# control.net
KiCad netlist of a schematic drawn in Altium Designer
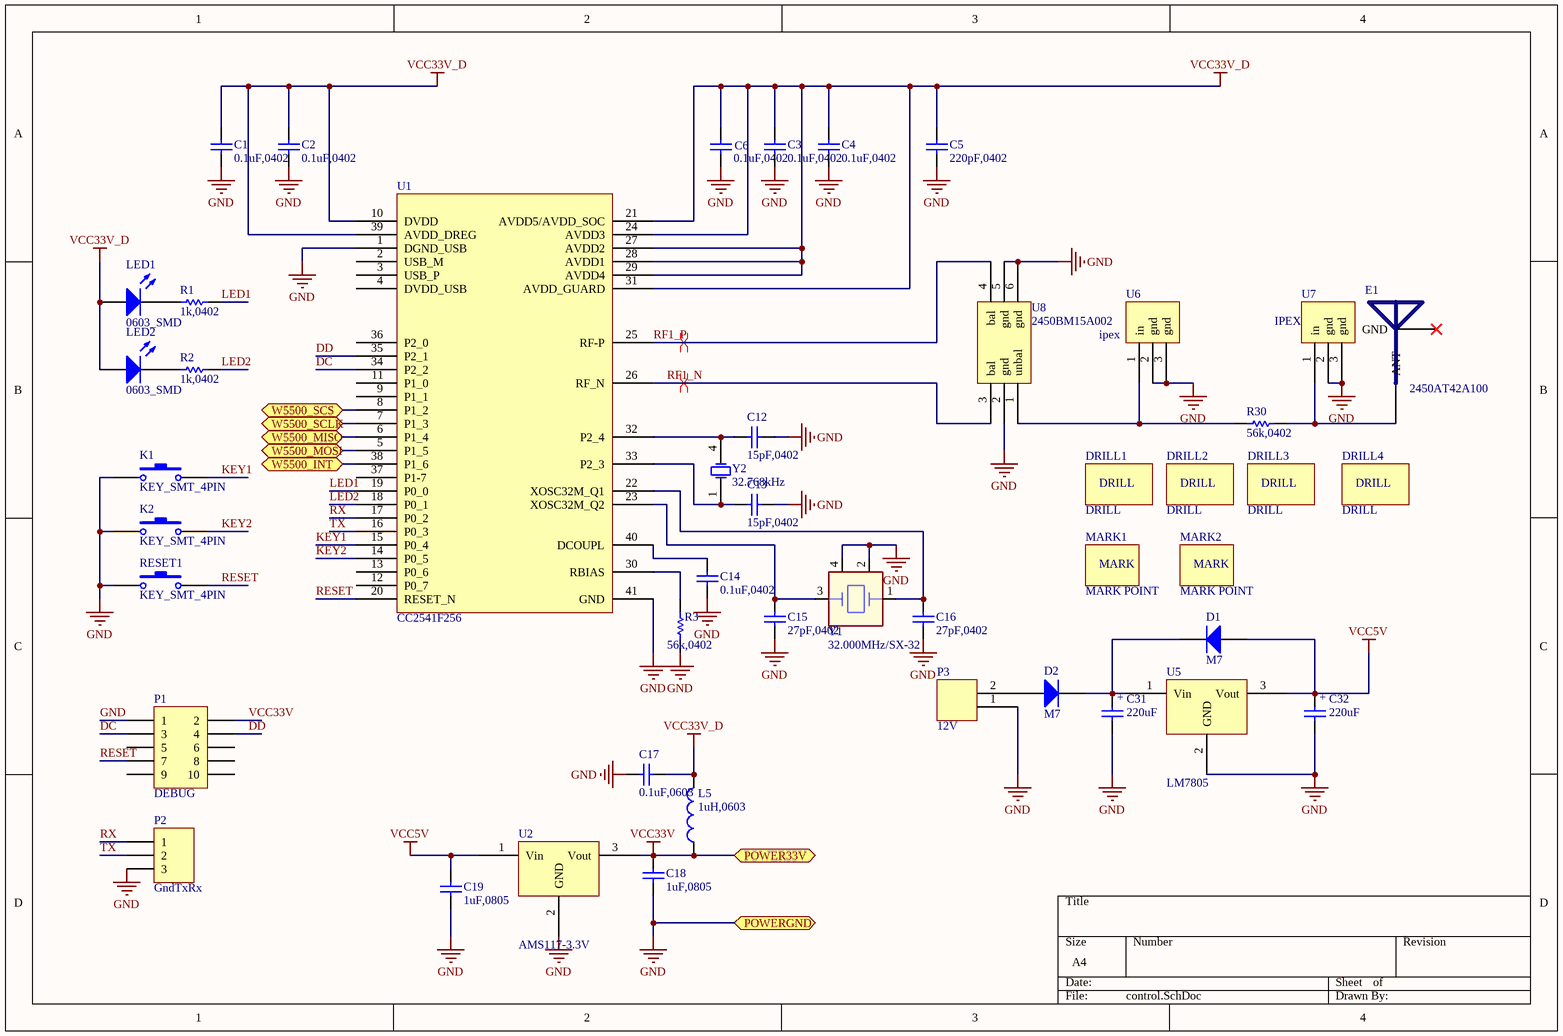
[diagram p0: control.SchDoc]

(export (version "E")
  (design (tool "Eeschema 10.0.6"))
  (components
    (comp (ref "C1")
      (value "0.1uF,0402")
      (footprint "C0402")
      (description "Capacitor")
      (fields (field (name "PUBLISHER") "Altium Limited"))
      (libsource (lib "Inte") (part "CAP"))
    )
    (comp (ref "C2")
      (value "0.1uF,0402")
      (footprint "C0402")
      (description "Capacitor")
      (fields (field (name "PUBLISHER") "Altium Limited"))
      (libsource (lib "Inte") (part "CAP"))
    )
    (comp (ref "C3")
      (value "0.1uF,0402")
      (footprint "C0402")
      (description "Capacitor")
      (fields (field (name "PUBLISHER") "Altium Limited"))
      (libsource (lib "Inte") (part "CAP"))
    )
    (comp (ref "C4")
      (value "0.1uF,0402")
      (footprint "C0402")
      (description "Capacitor")
      (fields (field (name "PUBLISHER") "Altium Limited"))
      (libsource (lib "Inte") (part "CAP"))
    )
    (comp (ref "C5")
      (value "220pF,0402")
      (footprint "C0402")
      (description "Capacitor")
      (fields (field (name "PUBLISHER") "Altium Limited"))
      (libsource (lib "Inte") (part "CAP"))
    )
    (comp (ref "C6")
      (value "0.1uF,0402")
      (footprint "C0402")
      (description "Capacitor")
      (fields (field (name "PUBLISHER") "Altium Limited"))
      (libsource (lib "Inte") (part "CAP"))
    )
    (comp (ref "C12")
      (value "15pF,0402")
      (footprint "C0402")
      (description "Capacitor")
      (fields (field (name "PUBLISHER") "Altium Limited"))
      (libsource (lib "Inte") (part "CAP"))
    )
    (comp (ref "C13")
      (value "15pF,0402")
      (footprint "C0402")
      (description "Capacitor")
      (fields (field (name "PUBLISHER") "Altium Limited"))
      (libsource (lib "Inte") (part "CAP"))
    )
    (comp (ref "C14")
      (value "0.1uF,0402")
      (footprint "C0402")
      (description "Capacitor")
      (fields (field (name "PUBLISHER") "Altium Limited"))
      (libsource (lib "Inte") (part "CAP"))
    )
    (comp (ref "C15")
      (value "27pF,0402")
      (footprint "C0402")
      (description "Capacitor")
      (fields (field (name "PUBLISHER") "Altium Limited"))
      (libsource (lib "Inte") (part "CAP"))
    )
    (comp (ref "C16")
      (value "27pF,0402")
      (footprint "C0402")
      (description "Capacitor")
      (fields (field (name "PUBLISHER") "Altium Limited"))
      (libsource (lib "Inte") (part "CAP"))
    )
    (comp (ref "C17")
      (value "0.1uF,0603")
      (footprint "C0603")
      (description "Capacitor")
      (fields (field (name "PUBLISHER") "Altium Limited"))
      (libsource (lib "Inte") (part "CAP"))
    )
    (comp (ref "C18")
      (value "1uF,0805")
      (footprint "C0805")
      (description "Capacitor")
      (fields (field (name "PUBLISHER") "Altium Limited"))
      (libsource (lib "Inte") (part "CAP"))
    )
    (comp (ref "C19")
      (value "1uF,0805")
      (footprint "C0805")
      (description "Capacitor")
      (fields (field (name "PUBLISHER") "Altium Limited"))
      (libsource (lib "Inte") (part "CAP"))
    )
    (comp (ref "C31")
      (value "220uF")
      (footprint "CDIP2")
      (description "electric capacitor")
      (libsource (lib "Inte") (part "E_CAP"))
    )
    (comp (ref "C32")
      (value "220uF")
      (footprint "CDIP2")
      (description "electric capacitor")
      (libsource (lib "Inte") (part "E_CAP"))
    )
    (comp (ref "D1")
      (value "M7")
      (footprint "DO214AC")
      (description "diode")
      (libsource (lib "Inte") (part "DIODE"))
    )
    (comp (ref "D2")
      (value "M7")
      (footprint "DO214AC")
      (description "diode")
      (libsource (lib "Inte") (part "DIODE"))
    )
    (comp (ref "DRILL1") (value "DRILL") (footprint "DRILL_3MM") (libsource (lib "Inte") (part "DRILL")))
    (comp (ref "DRILL2") (value "DRILL") (footprint "DRILL_3MM") (libsource (lib "Inte") (part "DRILL")))
    (comp (ref "DRILL3") (value "DRILL") (footprint "DRILL_3MM") (libsource (lib "Inte") (part "DRILL")))
    (comp (ref "DRILL4") (value "DRILL") (footprint "DRILL_3MM") (libsource (lib "Inte") (part "DRILL")))
    (comp (ref "E1")
      (value "2450AT42A100")
      (footprint "BT_ANT_PCB")
      (libsource (lib "Inte") (part "BT_ANT_PCB"))
    )
    (comp (ref "K1")
      (value "KEY_SMT_4PIN")
      (footprint "KEY-SMT")
      (description "key")
      (libsource (lib "Inte") (part "KEY"))
    )
    (comp (ref "K2")
      (value "KEY_SMT_4PIN")
      (footprint "KEY-SMT")
      (description "key")
      (libsource (lib "Inte") (part "KEY"))
    )
    (comp (ref "L5")
      (value "1uH,0603")
      (footprint "L0603")
      (description "Inductor")
      (fields (field (name "PUBLISHER") "Altium Limited"))
      (libsource (lib "Inte") (part "Inductor"))
    )
    (comp (ref "LED1")
      (value "0603_SMD")
      (footprint "LED0603")
      (description "led")
      (libsource (lib "Inte") (part "LED"))
    )
    (comp (ref "LED2")
      (value "0603_SMD")
      (footprint "LED0603")
      (description "led")
      (libsource (lib "Inte") (part "LED"))
    )
    (comp (ref "MARK1")
      (value "MARK POINT")
      (footprint "MARK_POINT")
      (libsource (lib "Inte") (part "MARK_POINT"))
    )
    (comp (ref "MARK2")
      (value "MARK POINT")
      (footprint "MARK_POINT")
      (libsource (lib "Inte") (part "MARK_POINT"))
    )
    (comp (ref "P1")
      (value "DEBUG")
      (footprint "HDR2X5")
      (description "Header, 5-Pin, Dual row")
      (fields (field (name "PUBLISHER") "Altium Limited"))
      (libsource (lib "Inte") (part "Header 5X2"))
    )
    (comp (ref "P2")
      (value "GndTxRx")
      (footprint "HDR1X3")
      (description "Header, 3-Pin")
      (fields (field (name "PUBLISHER") "Altium Limited"))
      (libsource (lib "Miscellaneous Connectors") (part "Header 3"))
    )
    (comp (ref "P3") (value "12V") (footprint "2EDG-5.08-2P") (libsource (lib "Inte") (part "2EDG-5.08-2P")))
    (comp (ref "R1")
      (value "1k,0402")
      (footprint "R0402")
      (description "Resistor")
      (fields (field (name "PUBLISHER") "Altium Limited"))
      (libsource (lib "Inte") (part "Res1"))
    )
    (comp (ref "R2")
      (value "1k,0402")
      (footprint "R0402")
      (description "Resistor")
      (fields (field (name "PUBLISHER") "Altium Limited"))
      (libsource (lib "Inte") (part "Res1"))
    )
    (comp (ref "R3")
      (value "56k,0402")
      (footprint "R0402")
      (description "Resistor")
      (fields (field (name "PUBLISHER") "Altium Limited"))
      (libsource (lib "Inte") (part "Res1"))
    )
    (comp (ref "R30")
      (value "56k,0402")
      (footprint "R0805")
      (description "Resistor")
      (fields (field (name "PUBLISHER") "Altium Limited"))
      (libsource (lib "Inte") (part "Res1"))
    )
    (comp (ref "RESET1")
      (value "KEY_SMT_4PIN")
      (footprint "KEY-SMT")
      (description "key")
      (libsource (lib "Inte") (part "KEY"))
    )
    (comp (ref "U1")
      (value "CC2541F256")
      (footprint "PQFP40")
      (description "TI cc2541F256")
      (libsource (lib "Inte") (part "CC254x"))
    )
    (comp (ref "U2")
      (value "AMS117-3.3V")
      (footprint "SOT223")
      (description "voltage regulator tube")
      (libsource (lib "Inte") (part "VOLT_REG"))
    )
    (comp (ref "U5")
      (value "LM7805")
      (footprint "SOT252")
      (description "voltage regulator tube")
      (libsource (lib "Inte") (part "VOLT_REG"))
    )
    (comp (ref "U6") (value "ipex") (footprint "IPEX") (libsource (lib "Inte") (part "IPEX")))
    (comp (ref "U7") (value "IPEX") (footprint "IPEX") (libsource (lib "Inte") (part "IPEX")))
    (comp (ref "U8")
      (value "2450BM15A002")
      (footprint "2450BM15A002")
      (libsource (lib "Inte") (part "2450BM15A002"))
    )
    (comp (ref "Y1")
      (value "32.000MHz/SX-32")
      (footprint "3225")
      (description "SPXO")
      (libsource (lib "Inte") (part "CRYSTAL_5"))
    )
    (comp (ref "Y2")
      (value "32.768kHz")
      (footprint "1206")
      (description "crystal")
      (libsource (lib "Inte") (part "DA740C"))
    )
  )
  (nets
    (net (code "1") (name "/DC") (class "Default")
      (node (ref "P1") (pin "3") (pinfunction "3_3") (pintype "passive"))
      (node (ref "U1") (pin "34") (pinfunction "P2_2_34") (pintype "passive"))
    )
    (net (code "2") (name "/DD") (class "Default")
      (node (ref "P1") (pin "4") (pinfunction "4_4") (pintype "passive"))
      (node (ref "U1") (pin "35") (pinfunction "P2_1_35") (pintype "passive"))
    )
    (net (code "3") (name "/KEY1") (class "Default")
      (node (ref "K1") (pin "2") (pinfunction "2_2") (pintype "passive"))
      (node (ref "U1") (pin "15") (pinfunction "P0_4_15") (pintype "passive"))
    )
    (net (code "4") (name "/KEY2") (class "Default")
      (node (ref "K2") (pin "2") (pinfunction "2_2") (pintype "passive"))
      (node (ref "U1") (pin "14") (pinfunction "P0_5_14") (pintype "passive"))
    )
    (net (code "5") (name "/LED1") (class "Default")
      (node (ref "R1") (pin "2") (pinfunction "2_2") (pintype "passive"))
      (node (ref "U1") (pin "19") (pinfunction "P0_0_19") (pintype "passive"))
    )
    (net (code "6") (name "/LED2") (class "Default")
      (node (ref "R2") (pin "2") (pinfunction "2_2") (pintype "passive"))
      (node (ref "U1") (pin "18") (pinfunction "P0_1_18") (pintype "passive"))
    )
    (net (code "7") (name "/RESET") (class "Default")
      (node (ref "P1") (pin "7") (pinfunction "7_7") (pintype "passive"))
      (node (ref "RESET1") (pin "2") (pinfunction "2_2") (pintype "passive"))
      (node (ref "U1") (pin "20") (pinfunction "RESET_N_20") (pintype "passive"))
    )
    (net (code "8") (name "/RF1_N") (class "Default")
      (node (ref "U1") (pin "26") (pinfunction "RF_N_26") (pintype "passive"))
      (node (ref "U8") (pin "3") (pinfunction "bal_3") (pintype "passive"))
    )
    (net (code "9") (name "/RF1_P") (class "Default")
      (node (ref "U1") (pin "25") (pinfunction "RF-P_25") (pintype "passive"))
      (node (ref "U8") (pin "4") (pinfunction "bal_4") (pintype "passive"))
    )
    (net (code "10") (name "/RX") (class "Default")
      (node (ref "P2") (pin "1") (pinfunction "1_1") (pintype "passive"))
      (node (ref "U1") (pin "17") (pinfunction "P0_2_17") (pintype "passive"))
    )
    (net (code "11") (name "/TX") (class "Default")
      (node (ref "P2") (pin "2") (pinfunction "2_2") (pintype "passive"))
      (node (ref "U1") (pin "16") (pinfunction "P0_3_16") (pintype "passive"))
    )
    (net (code "12") (name "/W5500_INT") (class "Default")
      (node (ref "U1") (pin "38") (pinfunction "P1_6_38") (pintype "passive"))
    )
    (net (code "13") (name "/W5500_MISO") (class "Default")
      (node (ref "U1") (pin "6") (pinfunction "P1_4_6") (pintype "passive"))
    )
    (net (code "14") (name "/W5500_MOSI") (class "Default")
      (node (ref "U1") (pin "5") (pinfunction "P1_5_5") (pintype "passive"))
    )
    (net (code "15") (name "/W5500_SCLK") (class "Default")
      (node (ref "U1") (pin "7") (pinfunction "P1_3_7") (pintype "passive"))
    )
    (net (code "16") (name "/W5500_SCS") (class "Default")
      (node (ref "U1") (pin "8") (pinfunction "P1_2_8") (pintype "passive"))
    )
    (net (code "17") (name "GND") (class "Default")
      (node (ref "C1") (pin "1") (pinfunction "1_1") (pintype "passive"))
      (node (ref "C12") (pin "1") (pinfunction "1_1") (pintype "passive"))
      (node (ref "C13") (pin "1") (pinfunction "1_1") (pintype "passive"))
      (node (ref "C14") (pin "1") (pinfunction "1_1") (pintype "passive"))
      (node (ref "C15") (pin "1") (pinfunction "1_1") (pintype "passive"))
      (node (ref "C16") (pin "1") (pinfunction "1_1") (pintype "passive"))
      (node (ref "C17") (pin "2") (pinfunction "2_2") (pintype "passive"))
      (node (ref "C18") (pin "1") (pinfunction "1_1") (pintype "passive"))
      (node (ref "C19") (pin "1") (pinfunction "1_1") (pintype "passive"))
      (node (ref "C2") (pin "1") (pinfunction "1_1") (pintype "passive"))
      (node (ref "C3") (pin "1") (pinfunction "1_1") (pintype "passive"))
      (node (ref "C31") (pin "2") (pinfunction "2_2") (pintype "passive"))
      (node (ref "C32") (pin "2") (pinfunction "2_2") (pintype "passive"))
      (node (ref "C4") (pin "1") (pinfunction "1_1") (pintype "passive"))
      (node (ref "C5") (pin "1") (pinfunction "1_1") (pintype "passive"))
      (node (ref "C6") (pin "2") (pinfunction "2_2") (pintype "passive"))
      (node (ref "K1") (pin "1") (pinfunction "1_1") (pintype "passive"))
      (node (ref "K2") (pin "1") (pinfunction "1_1") (pintype "passive"))
      (node (ref "P1") (pin "1") (pinfunction "1_1") (pintype "passive"))
      (node (ref "P2") (pin "3") (pinfunction "3_3") (pintype "passive"))
      (node (ref "P3") (pin "1") (pinfunction "1_1") (pintype "passive"))
      (node (ref "R3") (pin "1") (pinfunction "1_1") (pintype "passive"))
      (node (ref "RESET1") (pin "1") (pinfunction "1_1") (pintype "passive"))
      (node (ref "U1") (pin "1") (pinfunction "DGND_USB_1") (pintype "passive"))
      (node (ref "U1") (pin "41") (pinfunction "GND_41") (pintype "passive"))
      (node (ref "U2") (pin "2") (pinfunction "GND_2") (pintype "passive"))
      (node (ref "U5") (pin "2") (pinfunction "GND_2") (pintype "passive"))
      (node (ref "U6") (pin "2") (pinfunction "gnd_2") (pintype "passive"))
      (node (ref "U6") (pin "3") (pinfunction "gnd_3") (pintype "passive"))
      (node (ref "U7") (pin "2") (pinfunction "gnd_2") (pintype "passive"))
      (node (ref "U7") (pin "3") (pinfunction "gnd_3") (pintype "passive"))
      (node (ref "U8") (pin "2") (pinfunction "gnd_2") (pintype "passive"))
      (node (ref "U8") (pin "5") (pinfunction "gnd_5") (pintype "passive"))
      (node (ref "U8") (pin "6") (pinfunction "gnd_6") (pintype "passive"))
      (node (ref "Y1") (pin "2") (pinfunction "2_2") (pintype "passive"))
      (node (ref "Y1") (pin "4") (pinfunction "4_4") (pintype "passive"))
    )
    (net (code "18") (name "Net-(D1-K)") (class "Default")
      (node (ref "C31") (pin "1") (pinfunction "1_1") (pintype "passive"))
      (node (ref "D1") (pin "2") (pinfunction "K_2") (pintype "passive"))
      (node (ref "D2") (pin "2") (pinfunction "K_2") (pintype "passive"))
      (node (ref "U5") (pin "1") (pinfunction "Vin_1") (pintype "passive"))
    )
    (net (code "19") (name "Net-(D2-A)") (class "Default")
      (node (ref "D2") (pin "1") (pinfunction "A_1") (pintype "passive"))
      (node (ref "P3") (pin "2") (pinfunction "2_2") (pintype "passive"))
    )
    (net (code "20") (name "Net-(E1-ANT)") (class "Default")
      (node (ref "E1") (pin "1") (pinfunction "ANT_1") (pintype "passive"))
      (node (ref "R30") (pin "2") (pinfunction "2_2") (pintype "passive"))
      (node (ref "U7") (pin "1") (pinfunction "in_1") (pintype "passive"))
    )
    (net (code "21") (name "Net-(LED1-K)") (class "Default")
      (node (ref "LED1") (pin "2") (pinfunction "K_2") (pintype "passive"))
      (node (ref "R1") (pin "1") (pinfunction "1_1") (pintype "passive"))
    )
    (net (code "22") (name "Net-(LED2-K)") (class "Default")
      (node (ref "LED2") (pin "2") (pinfunction "K_2") (pintype "passive"))
      (node (ref "R2") (pin "1") (pinfunction "1_1") (pintype "passive"))
    )
    (net (code "23") (name "Net-(U1-DCOUPL)") (class "Default")
      (node (ref "C14") (pin "2") (pinfunction "2_2") (pintype "passive"))
      (node (ref "U1") (pin "40") (pinfunction "DCOUPL_40") (pintype "passive"))
    )
    (net (code "24") (name "Net-(U1-P2_3)") (class "Default")
      (node (ref "C13") (pin "2") (pinfunction "2_2") (pintype "passive"))
      (node (ref "U1") (pin "33") (pinfunction "P2_3_33") (pintype "passive"))
      (node (ref "Y2") (pin "1") (pinfunction "OSC1_1") (pintype "passive"))
    )
    (net (code "25") (name "Net-(U1-P2_4)") (class "Default")
      (node (ref "C12") (pin "2") (pinfunction "2_2") (pintype "passive"))
      (node (ref "U1") (pin "32") (pinfunction "P2_4_32") (pintype "passive"))
      (node (ref "Y2") (pin "4") (pinfunction "OSC2_4") (pintype "passive"))
    )
    (net (code "26") (name "Net-(U1-RBIAS)") (class "Default")
      (node (ref "R3") (pin "2") (pinfunction "2_2") (pintype "passive"))
      (node (ref "U1") (pin "30") (pinfunction "RBIAS_30") (pintype "passive"))
    )
    (net (code "27") (name "Net-(U1-XOSC32M_Q1)") (class "Default")
      (node (ref "C16") (pin "2") (pinfunction "2_2") (pintype "passive"))
      (node (ref "U1") (pin "22") (pinfunction "XOSC32M_Q1_22") (pintype "passive"))
      (node (ref "Y1") (pin "1") (pinfunction "1_1") (pintype "passive"))
    )
    (net (code "28") (name "Net-(U1-XOSC32M_Q2)") (class "Default")
      (node (ref "C15") (pin "2") (pinfunction "2_2") (pintype "passive"))
      (node (ref "U1") (pin "23") (pinfunction "XOSC32M_Q2_23") (pintype "passive"))
      (node (ref "Y1") (pin "3") (pinfunction "3_3") (pintype "passive"))
    )
    (net (code "29") (name "Net-(U6-in)") (class "Default")
      (node (ref "R30") (pin "1") (pinfunction "1_1") (pintype "passive"))
      (node (ref "U6") (pin "1") (pinfunction "in_1") (pintype "passive"))
      (node (ref "U8") (pin "1") (pinfunction "unbal_1") (pintype "passive"))
    )
    (net (code "30") (name "VCC5V") (class "Default")
      (node (ref "C19") (pin "2") (pinfunction "2_2") (pintype "passive"))
      (node (ref "C32") (pin "1") (pinfunction "1_1") (pintype "passive"))
      (node (ref "D1") (pin "1") (pinfunction "A_1") (pintype "passive"))
      (node (ref "U2") (pin "1") (pinfunction "Vin_1") (pintype "passive"))
      (node (ref "U5") (pin "3") (pinfunction "Vout_3") (pintype "passive"))
    )
    (net (code "31") (name "VCC33V") (class "Default")
      (node (ref "C18") (pin "2") (pinfunction "2_2") (pintype "passive"))
      (node (ref "L5") (pin "1") (pinfunction "1_1") (pintype "passive"))
      (node (ref "P1") (pin "2") (pinfunction "2_2") (pintype "passive"))
      (node (ref "U2") (pin "3") (pinfunction "Vout_3") (pintype "passive"))
    )
    (net (code "32") (name "VCC33V_D") (class "Default")
      (node (ref "C1") (pin "2") (pinfunction "2_2") (pintype "passive"))
      (node (ref "C17") (pin "1") (pinfunction "1_1") (pintype "passive"))
      (node (ref "C2") (pin "2") (pinfunction "2_2") (pintype "passive"))
      (node (ref "C3") (pin "2") (pinfunction "2_2") (pintype "passive"))
      (node (ref "C4") (pin "2") (pinfunction "2_2") (pintype "passive"))
      (node (ref "C5") (pin "2") (pinfunction "2_2") (pintype "passive"))
      (node (ref "C6") (pin "1") (pinfunction "1_1") (pintype "passive"))
      (node (ref "L5") (pin "2") (pinfunction "2_2") (pintype "passive"))
      (node (ref "LED1") (pin "1") (pinfunction "A_1") (pintype "passive"))
      (node (ref "LED2") (pin "1") (pinfunction "A_1") (pintype "passive"))
      (node (ref "U1") (pin "10") (pinfunction "DVDD_10") (pintype "passive"))
      (node (ref "U1") (pin "21") (pinfunction "AVDD5/AVDD_SOC_21") (pintype "passive"))
      (node (ref "U1") (pin "24") (pinfunction "AVDD3_24") (pintype "passive"))
      (node (ref "U1") (pin "27") (pinfunction "AVDD2_27") (pintype "passive"))
      (node (ref "U1") (pin "28") (pinfunction "AVDD1_28") (pintype "passive"))
      (node (ref "U1") (pin "29") (pinfunction "AVDD4_29") (pintype "passive"))
      (node (ref "U1") (pin "31") (pinfunction "AVDD_GUARD_31") (pintype "passive"))
      (node (ref "U1") (pin "39") (pinfunction "AVDD_DREG_39") (pintype "passive"))
    )
    (net (code "33") (name "unconnected-(E1-GND-Pad2)") (class "Default")
      (node (ref "E1") (pin "2") (pinfunction "GND_2") (pintype "passive+no_connect"))
    )
    (net (code "34") (name "unconnected-(P1-Pad5)") (class "Default")
      (node (ref "P1") (pin "5") (pinfunction "5_5") (pintype "passive"))
    )
    (net (code "35") (name "unconnected-(P1-Pad6)") (class "Default")
      (node (ref "P1") (pin "6") (pinfunction "6_6") (pintype "passive"))
    )
    (net (code "36") (name "unconnected-(P1-Pad8)") (class "Default")
      (node (ref "P1") (pin "8") (pinfunction "8_8") (pintype "passive"))
    )
    (net (code "37") (name "unconnected-(P1-Pad9)") (class "Default")
      (node (ref "P1") (pin "9") (pinfunction "9_9") (pintype "passive"))
    )
    (net (code "38") (name "unconnected-(P1-Pad10)") (class "Default")
      (node (ref "P1") (pin "10") (pinfunction "10_10") (pintype "passive"))
    )
    (net (code "39") (name "unconnected-(U1-DVDD_USB-Pad4)") (class "Default")
      (node (ref "U1") (pin "4") (pinfunction "DVDD_USB_4") (pintype "passive"))
    )
    (net (code "40") (name "unconnected-(U1-P0_6-Pad13)") (class "Default")
      (node (ref "U1") (pin "13") (pinfunction "P0_6_13") (pintype "passive"))
    )
    (net (code "41") (name "unconnected-(U1-P0_7-Pad12)") (class "Default")
      (node (ref "U1") (pin "12") (pinfunction "P0_7_12") (pintype "passive"))
    )
    (net (code "42") (name "unconnected-(U1-P1-7-Pad37)") (class "Default")
      (node (ref "U1") (pin "37") (pinfunction "P1-7_37") (pintype "passive"))
    )
    (net (code "43") (name "unconnected-(U1-P1_0-Pad11)") (class "Default")
      (node (ref "U1") (pin "11") (pinfunction "P1_0_11") (pintype "passive"))
    )
    (net (code "44") (name "unconnected-(U1-P1_1-Pad9)") (class "Default")
      (node (ref "U1") (pin "9") (pinfunction "P1_1_9") (pintype "passive"))
    )
    (net (code "45") (name "unconnected-(U1-P2_0-Pad36)") (class "Default")
      (node (ref "U1") (pin "36") (pinfunction "P2_0_36") (pintype "passive"))
    )
    (net (code "46") (name "unconnected-(U1-USB_M-Pad2)") (class "Default")
      (node (ref "U1") (pin "2") (pinfunction "USB_M_2") (pintype "passive"))
    )
    (net (code "47") (name "unconnected-(U1-USB_P-Pad3)") (class "Default")
      (node (ref "U1") (pin "3") (pinfunction "USB_P_3") (pintype "passive"))
    )
  )
)
